# POWER_PCie.net
KiCad netlist of a schematic drawn in Altium Designer
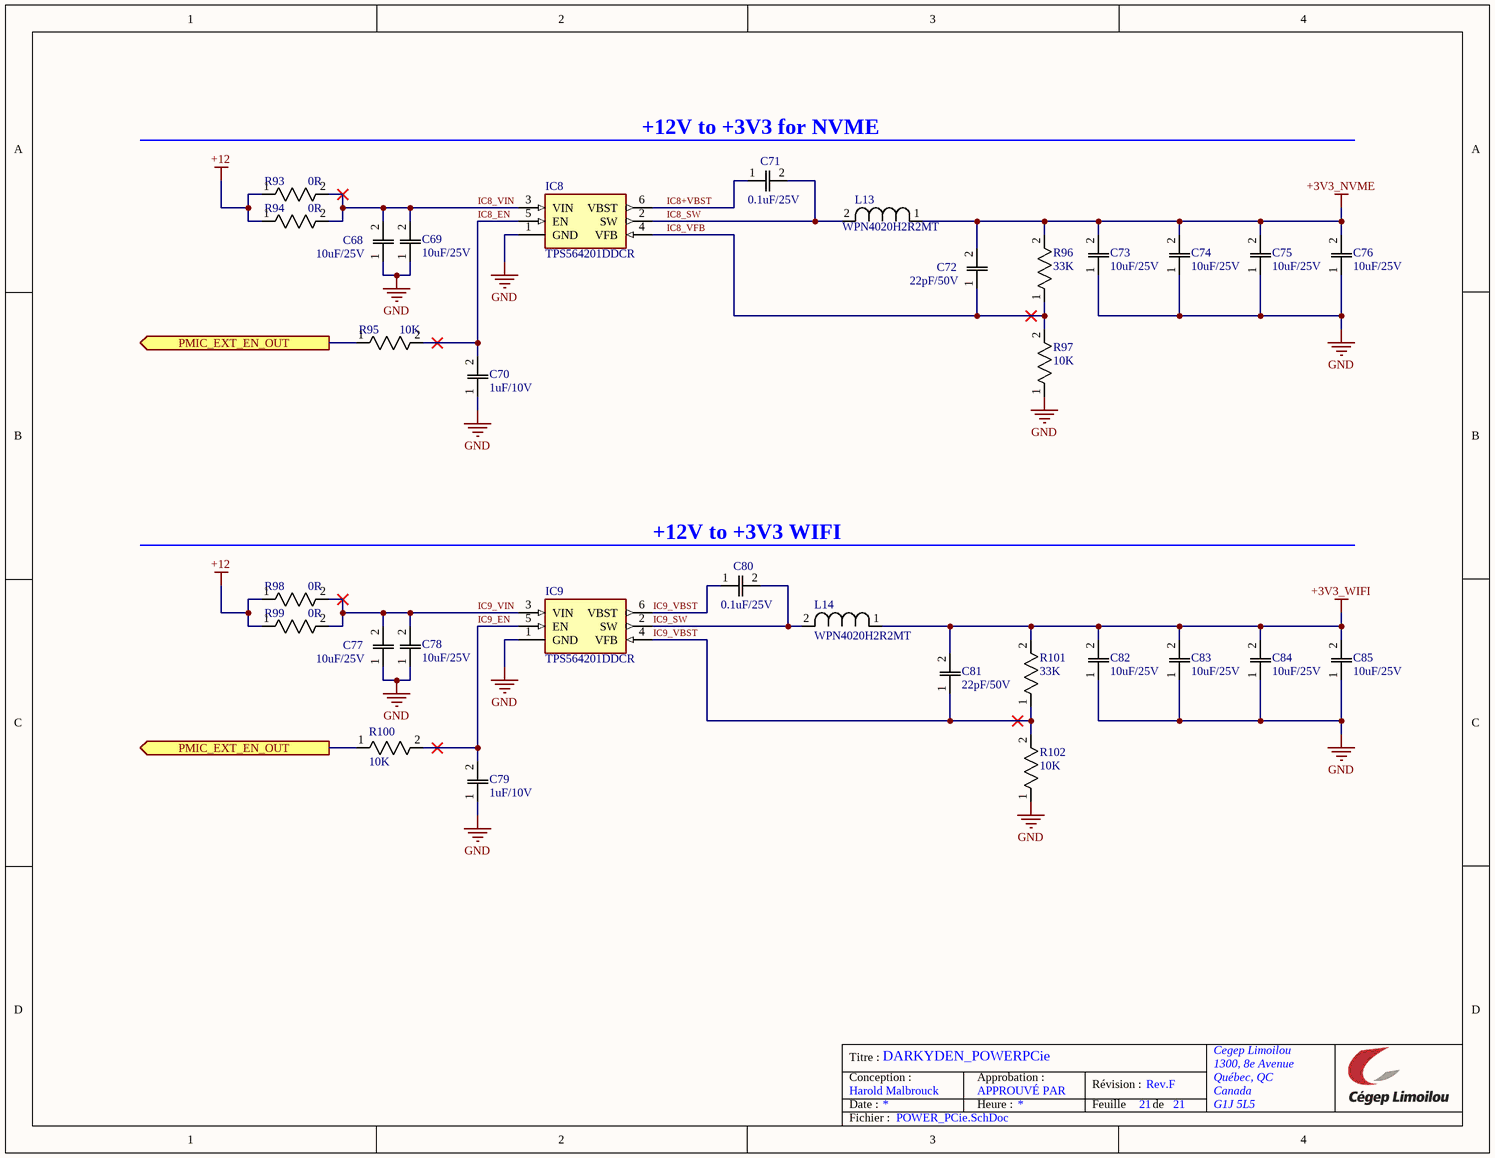
[diagram p0: POWER_PCie.SchDoc]

(export (version "E")
  (design (tool "Eeschema 10.0.6"))
  (components
    (comp (ref "C68")
      (value "10uF/25V")
      (footprint "C0805")
      (description "10uF / 25 VDC, +85degC, X5R Dielec, +/-10% ¦ KEMET C0805C106K3PACTU 0805")
      (fields
        (field (name "MANUFACTURER") "KEMET")
        (field (name "MANUFACTURER PART NUMBER") "C0805C106K3PACTU")
      )
      (libsource (lib "DARKYDEN") (part "C0805C106K3PACTU"))
    )
    (comp (ref "C69")
      (value "10uF/25V")
      (footprint "C0805")
      (description "10uF / 25 VDC, +85degC, X5R Dielec, +/-10% ¦ KEMET C0805C106K3PACTU 0805")
      (fields
        (field (name "MANUFACTURER") "KEMET")
        (field (name "MANUFACTURER PART NUMBER") "C0805C106K3PACTU")
      )
      (libsource (lib "DARKYDEN") (part "C0805C106K3PACTU"))
    )
    (comp (ref "C70")
      (value "1uF/10V")
      (footprint "C0805")
      (description "Multilayer Ceramic Capacitors MLCC - SMD/SMT 10V 1uF X7R 0805 10%")
      (fields
        (field (name "MANUFACTURER") "KEMET")
        (field (name "MANUFACTURER PART NUMBER") "C0805C105K3RACTU")
      )
      (libsource (lib "DARKYDEN") (part "C0805C105K8RACTU"))
    )
    (comp (ref "C71")
      (value "0.1uF/25V")
      (footprint "c0805")
      (description "0.1uF 25V X7R 10% SMD 0805 125C Plastic T/R")
      (fields
        (field (name "MANUFACTURER") "KEMET")
        (field (name "MANUFACTURER PART NUMBER") "C0805C104K5RACTU")
      )
      (libsource (lib "DARKYDEN") (part "C0805C104K3RACTU"))
    )
    (comp (ref "C72")
      (value "22pF/50V")
      (footprint "C0805")
      (description "Cap Ceramic 22pF 50V X7R 5% Pad SMD 0805 125°C T/R")
      (fields
        (field (name "MANUFACTURER") "KEMET")
        (field (name "MANUFACTURER PART NUMBER") "C0805C220J5RACTU")
      )
      (libsource (lib "DARKYDEN") (part "C0805C220J5RACTU"))
    )
    (comp (ref "C73")
      (value "10uF/25V")
      (footprint "C0805")
      (description "10uF / 25 VDC, +85degC, X5R Dielec, +/-10% ¦ KEMET C0805C106K3PACTU 0805")
      (fields
        (field (name "MANUFACTURER") "KEMET")
        (field (name "MANUFACTURER PART NUMBER") "C0805C106K3PACTU")
      )
      (libsource (lib "DARKYDEN") (part "C0805C106K3PACTU"))
    )
    (comp (ref "C74")
      (value "10uF/25V")
      (footprint "C0805")
      (description "10uF / 25 VDC, +85degC, X5R Dielec, +/-10% ¦ KEMET C0805C106K3PACTU 0805")
      (fields
        (field (name "MANUFACTURER") "KEMET")
        (field (name "MANUFACTURER PART NUMBER") "C0805C106K3PACTU")
      )
      (libsource (lib "DARKYDEN") (part "C0805C106K3PACTU"))
    )
    (comp (ref "C75")
      (value "10uF/25V")
      (footprint "C0805")
      (description "10uF / 25 VDC, +85degC, X5R Dielec, +/-10% ¦ KEMET C0805C106K3PACTU 0805")
      (fields
        (field (name "MANUFACTURER") "KEMET")
        (field (name "MANUFACTURER PART NUMBER") "C0805C106K3PACTU")
      )
      (libsource (lib "DARKYDEN") (part "C0805C106K3PACTU"))
    )
    (comp (ref "C76")
      (value "10uF/25V")
      (footprint "C0805")
      (description "10uF / 25 VDC, +85degC, X5R Dielec, +/-10% ¦ KEMET C0805C106K3PACTU 0805")
      (fields
        (field (name "MANUFACTURER") "KEMET")
        (field (name "MANUFACTURER PART NUMBER") "C0805C106K3PACTU")
      )
      (libsource (lib "DARKYDEN") (part "C0805C106K3PACTU"))
    )
    (comp (ref "C77")
      (value "10uF/25V")
      (footprint "C0805")
      (description "10uF / 25 VDC, +85degC, X5R Dielec, +/-10% ¦ KEMET C0805C106K3PACTU 0805")
      (fields
        (field (name "MANUFACTURER") "KEMET")
        (field (name "MANUFACTURER PART NUMBER") "C0805C106K3PACTU")
      )
      (libsource (lib "DARKYDEN") (part "C0805C106K3PACTU"))
    )
    (comp (ref "C78")
      (value "10uF/25V")
      (footprint "C0805")
      (description "10uF / 25 VDC, +85degC, X5R Dielec, +/-10% ¦ KEMET C0805C106K3PACTU 0805")
      (fields
        (field (name "MANUFACTURER") "KEMET")
        (field (name "MANUFACTURER PART NUMBER") "C0805C106K3PACTU")
      )
      (libsource (lib "DARKYDEN") (part "C0805C106K3PACTU"))
    )
    (comp (ref "C79")
      (value "1uF/10V")
      (footprint "C0805")
      (description "Multilayer Ceramic Capacitors MLCC - SMD/SMT 10V 1uF X7R 0805 10%")
      (fields
        (field (name "MANUFACTURER") "KEMET")
        (field (name "MANUFACTURER PART NUMBER") "C0805C105K3RACTU")
      )
      (libsource (lib "DARKYDEN") (part "C0805C105K8RACTU"))
    )
    (comp (ref "C80")
      (value "0.1uF/25V")
      (footprint "c0805")
      (description "0.1uF 25V X7R 10% SMD 0805 125C Plastic T/R")
      (fields
        (field (name "MANUFACTURER") "KEMET")
        (field (name "MANUFACTURER PART NUMBER") "C0805C104K5RACTU")
      )
      (libsource (lib "DARKYDEN") (part "C0805C104K3RACTU"))
    )
    (comp (ref "C81")
      (value "22pF/50V")
      (footprint "C0805")
      (description "Cap Ceramic 22pF 50V X7R 5% Pad SMD 0805 125°C T/R")
      (fields
        (field (name "MANUFACTURER") "KEMET")
        (field (name "MANUFACTURER PART NUMBER") "C0805C220J5RACTU")
      )
      (libsource (lib "DARKYDEN") (part "C0805C220J5RACTU"))
    )
    (comp (ref "C82")
      (value "10uF/25V")
      (footprint "C0805")
      (description "10uF / 25 VDC, +85degC, X5R Dielec, +/-10% ¦ KEMET C0805C106K3PACTU 0805")
      (fields
        (field (name "MANUFACTURER") "KEMET")
        (field (name "MANUFACTURER PART NUMBER") "C0805C106K3PACTU")
      )
      (libsource (lib "DARKYDEN") (part "C0805C106K3PACTU"))
    )
    (comp (ref "C83")
      (value "10uF/25V")
      (footprint "C0805")
      (description "10uF / 25 VDC, +85degC, X5R Dielec, +/-10% ¦ KEMET C0805C106K3PACTU 0805")
      (fields
        (field (name "MANUFACTURER") "KEMET")
        (field (name "MANUFACTURER PART NUMBER") "C0805C106K3PACTU")
      )
      (libsource (lib "DARKYDEN") (part "C0805C106K3PACTU"))
    )
    (comp (ref "C84")
      (value "10uF/25V")
      (footprint "C0805")
      (description "10uF / 25 VDC, +85degC, X5R Dielec, +/-10% ¦ KEMET C0805C106K3PACTU 0805")
      (fields
        (field (name "MANUFACTURER") "KEMET")
        (field (name "MANUFACTURER PART NUMBER") "C0805C106K3PACTU")
      )
      (libsource (lib "DARKYDEN") (part "C0805C106K3PACTU"))
    )
    (comp (ref "C85")
      (value "10uF/25V")
      (footprint "C0805")
      (description "10uF / 25 VDC, +85degC, X5R Dielec, +/-10% ¦ KEMET C0805C106K3PACTU 0805")
      (fields
        (field (name "MANUFACTURER") "KEMET")
        (field (name "MANUFACTURER PART NUMBER") "C0805C106K3PACTU")
      )
      (libsource (lib "DARKYDEN") (part "C0805C106K3PACTU"))
    )
    (comp (ref "IC8")
      (value "TPS564201DDCR")
      (footprint "SamacSys:SOT95P280X110-6N")
      (fields
        (field (name "MOUSER PART NUMBER") "595-TPS564201DDCR")
        (field (name "MANUFACTURER") "Texas Instruments")
      )
      (libsource (lib "SamacSys") (part "TPS564201DDCR"))
    )
    (comp (ref "IC9")
      (value "TPS564201DDCR")
      (footprint "SamacSys:SOT95P280X110-6N")
      (fields
        (field (name "MOUSER PART NUMBER") "595-TPS564201DDCR")
        (field (name "MANUFACTURER") "Texas Instruments")
      )
      (libsource (lib "SamacSys") (part "TPS564201DDCR"))
    )
    (comp (ref "L13")
      (value "WPN4020H2R2MT")
      (footprint "WPN4020H2R2MT:IND_WPN4020H_SNL")
      (description "2.2 µH Shielded Drum Core, Wirewound Inductor 4.3 A 48mOhm Max Nonstandard")
      (fields (field (name "MANUFACTURER") "Sunlord"))
      (libsource (lib "DARKYDEN") (part "WPN4020H2R2MT"))
    )
    (comp (ref "L14")
      (value "WPN4020H2R2MT")
      (footprint "WPN4020H2R2MT:IND_WPN4020H_SNL")
      (description "2.2 µH Shielded Drum Core, Wirewound Inductor 4.3 A 48mOhm Max Nonstandard")
      (fields (field (name "MANUFACTURER") "Sunlord"))
      (libsource (lib "DARKYDEN") (part "WPN4020H2R2MT"))
    )
    (comp (ref "R93")
      (value "0R")
      (footprint "SamacSys:RESC1608X55N")
      (description "Zero Ohm Resistor, Jumper, 0603 [1608 Metric], Thick Film, 100 mW, 1 A, Surface Mount")
      (fields
        (field (name "MOUSER PART NUMBER") "667-ERJ-3GEY0R00V")
        (field (name "ARROW PART NUMBER") "ERJ-3GEY0R00V")
      )
      (libsource (lib "DARKYDEN") (part "ERJ-3GEY0R00V"))
    )
    (comp (ref "R94")
      (value "0R")
      (footprint "SamacSys:RESC1608X55N")
      (description "Zero Ohm Resistor, Jumper, 0603 [1608 Metric], Thick Film, 100 mW, 1 A, Surface Mount")
      (fields
        (field (name "MOUSER PART NUMBER") "667-ERJ-3GEY0R00V")
        (field (name "ARROW PART NUMBER") "ERJ-3GEY0R00V")
      )
      (libsource (lib "DARKYDEN") (part "ERJ-3GEY0R00V"))
    )
    (comp (ref "R95")
      (value "10K")
      (footprint "SamacSys:RESC1608X55N")
      (description "10K Ohm 5% Res Thick Film 0603  0.1W(1/10W) ±200ppm/C Pad SMD Automotive T/R")
      (fields
        (field (name "MOUSER PART NUMBER") "667-ERJ-3GEYJ103V")
        (field (name "ARROW PART NUMBER") "ERJ-3GEYJ103V")
      )
      (libsource (lib "DARKYDEN") (part "ERJ-3GEYJ103V"))
    )
    (comp (ref "R96")
      (value "33K")
      (footprint "SamacSys:RESC1608X55N")
      (description "33K Ohm 0603  5% 0.1W(1/10W) +/-200ppm/ßC SMD Automotive T/R")
      (fields
        (field (name "MOUSER PART NUMBER") "667-ERJ-3GEYJ333V")
        (field (name "MANUFACTURER") "Panasonic")
      )
      (libsource (lib "DARKYDEN") (part "ERJ-3GEYJ333V"))
    )
    (comp (ref "R97")
      (value "10K")
      (footprint "SamacSys:RESC1608X55N")
      (description "10K Ohm 5% Res Thick Film 0603  0.1W(1/10W) ±200ppm/C Pad SMD Automotive T/R")
      (fields
        (field (name "MOUSER PART NUMBER") "667-ERJ-3GEYJ103V")
        (field (name "ARROW PART NUMBER") "ERJ-3GEYJ103V")
      )
      (libsource (lib "DARKYDEN") (part "ERJ-3GEYJ103V"))
    )
    (comp (ref "R98")
      (value "0R")
      (footprint "SamacSys:RESC1608X55N")
      (description "Zero Ohm Resistor, Jumper, 0603 [1608 Metric], Thick Film, 100 mW, 1 A, Surface Mount")
      (fields
        (field (name "MOUSER PART NUMBER") "667-ERJ-3GEY0R00V")
        (field (name "ARROW PART NUMBER") "ERJ-3GEY0R00V")
      )
      (libsource (lib "DARKYDEN") (part "ERJ-3GEY0R00V"))
    )
    (comp (ref "R99")
      (value "0R")
      (footprint "SamacSys:RESC1608X55N")
      (description "Zero Ohm Resistor, Jumper, 0603 [1608 Metric], Thick Film, 100 mW, 1 A, Surface Mount")
      (fields
        (field (name "MOUSER PART NUMBER") "667-ERJ-3GEY0R00V")
        (field (name "ARROW PART NUMBER") "ERJ-3GEY0R00V")
      )
      (libsource (lib "DARKYDEN") (part "ERJ-3GEY0R00V"))
    )
    (comp (ref "R100")
      (value "10K")
      (footprint "SamacSys:RESC1608X55N")
      (description "10K Ohm 5% Res Thick Film 0603  0.1W(1/10W) ±200ppm/C Pad SMD Automotive T/R")
      (fields
        (field (name "MOUSER PART NUMBER") "667-ERJ-3GEYJ103V")
        (field (name "ARROW PART NUMBER") "ERJ-3GEYJ103V")
      )
      (libsource (lib "DARKYDEN") (part "ERJ-3GEYJ103V"))
    )
    (comp (ref "R101")
      (value "33K")
      (footprint "SamacSys:RESC1608X55N")
      (description "33K Ohm 0603  5% 0.1W(1/10W) +/-200ppm/ßC SMD Automotive T/R")
      (fields
        (field (name "MOUSER PART NUMBER") "667-ERJ-3GEYJ333V")
        (field (name "MANUFACTURER") "Panasonic")
      )
      (libsource (lib "DARKYDEN") (part "ERJ-3GEYJ333V"))
    )
    (comp (ref "R102")
      (value "10K")
      (footprint "SamacSys:RESC1608X55N")
      (description "10K Ohm 5% Res Thick Film 0603  0.1W(1/10W) ±200ppm/C Pad SMD Automotive T/R")
      (fields
        (field (name "MOUSER PART NUMBER") "667-ERJ-3GEYJ103V")
        (field (name "ARROW PART NUMBER") "ERJ-3GEYJ103V")
      )
      (libsource (lib "DARKYDEN") (part "ERJ-3GEYJ103V"))
    )
  )
  (nets
    (net (code "1") (name "+3V3_NVME") (class "Default")
      (node (ref "C72") (pin "2") (pinfunction "2_2") (pintype "passive"))
      (node (ref "C73") (pin "2") (pinfunction "2_2") (pintype "passive"))
      (node (ref "C74") (pin "2") (pinfunction "2_2") (pintype "passive"))
      (node (ref "C75") (pin "2") (pinfunction "2_2") (pintype "passive"))
      (node (ref "C76") (pin "2") (pinfunction "2_2") (pintype "passive"))
      (node (ref "L13") (pin "1") (pinfunction "1_1") (pintype "passive"))
      (node (ref "R96") (pin "2") (pinfunction "2_2") (pintype "passive"))
    )
    (net (code "2") (name "+3V3_WIFI") (class "Default")
      (node (ref "C81") (pin "2") (pinfunction "2_2") (pintype "passive"))
      (node (ref "C82") (pin "2") (pinfunction "2_2") (pintype "passive"))
      (node (ref "C83") (pin "2") (pinfunction "2_2") (pintype "passive"))
      (node (ref "C84") (pin "2") (pinfunction "2_2") (pintype "passive"))
      (node (ref "C85") (pin "2") (pinfunction "2_2") (pintype "passive"))
      (node (ref "L14") (pin "1") (pinfunction "1_1") (pintype "passive"))
      (node (ref "R101") (pin "2") (pinfunction "2_2") (pintype "passive"))
    )
    (net (code "3") (name "+12") (class "Default")
      (node (ref "R93") (pin "1") (pinfunction "1_1") (pintype "passive"))
      (node (ref "R94") (pin "1") (pinfunction "1_1") (pintype "passive"))
      (node (ref "R98") (pin "1") (pinfunction "1_1") (pintype "passive"))
      (node (ref "R99") (pin "1") (pinfunction "1_1") (pintype "passive"))
    )
    (net (code "4") (name "/IC8+VBST") (class "Default")
      (node (ref "C71") (pin "1") (pinfunction "1_1") (pintype "passive"))
      (node (ref "IC8") (pin "6") (pinfunction "VBST_6") (pintype "output"))
    )
    (net (code "5") (name "/IC8_EN") (class "Default")
      (node (ref "C70") (pin "2") (pinfunction "2_2") (pintype "passive"))
      (node (ref "IC8") (pin "5") (pinfunction "EN_5") (pintype "input"))
      (node (ref "R95") (pin "2") (pinfunction "2_2") (pintype "passive"))
    )
    (net (code "6") (name "/IC8_SW") (class "Default")
      (node (ref "C71") (pin "2") (pinfunction "2_2") (pintype "passive"))
      (node (ref "IC8") (pin "2") (pinfunction "SW_2") (pintype "output"))
      (node (ref "L13") (pin "2") (pinfunction "2_2") (pintype "passive"))
    )
    (net (code "7") (name "/IC8_VFB") (class "Default")
      (node (ref "C72") (pin "1") (pinfunction "1_1") (pintype "passive"))
      (node (ref "IC8") (pin "4") (pinfunction "VFB_4") (pintype "input"))
      (node (ref "R96") (pin "1") (pinfunction "1_1") (pintype "passive"))
      (node (ref "R97") (pin "2") (pinfunction "2_2") (pintype "passive"))
    )
    (net (code "8") (name "/IC8_VIN") (class "Default")
      (node (ref "C68") (pin "2") (pinfunction "2_2") (pintype "passive"))
      (node (ref "C69") (pin "2") (pinfunction "2_2") (pintype "passive"))
      (node (ref "IC8") (pin "3") (pinfunction "VIN_3") (pintype "input"))
      (node (ref "R93") (pin "2") (pinfunction "2_2") (pintype "passive"))
      (node (ref "R94") (pin "2") (pinfunction "2_2") (pintype "passive"))
    )
    (net (code "9") (name "/IC9_EN") (class "Default")
      (node (ref "C79") (pin "2") (pinfunction "2_2") (pintype "passive"))
      (node (ref "IC9") (pin "5") (pinfunction "EN_5") (pintype "input"))
      (node (ref "R100") (pin "2") (pinfunction "2_2") (pintype "passive"))
    )
    (net (code "10") (name "/IC9_SW") (class "Default")
      (node (ref "C80") (pin "2") (pinfunction "2_2") (pintype "passive"))
      (node (ref "IC9") (pin "2") (pinfunction "SW_2") (pintype "output"))
      (node (ref "L14") (pin "2") (pinfunction "2_2") (pintype "passive"))
    )
    (net (code "11") (name "/IC9_VBST") (class "Default")
      (node (ref "C80") (pin "1") (pinfunction "1_1") (pintype "passive"))
      (node (ref "C81") (pin "1") (pinfunction "1_1") (pintype "passive"))
      (node (ref "IC9") (pin "4") (pinfunction "VFB_4") (pintype "input"))
      (node (ref "IC9") (pin "6") (pinfunction "VBST_6") (pintype "output"))
      (node (ref "R101") (pin "1") (pinfunction "1_1") (pintype "passive"))
      (node (ref "R102") (pin "2") (pinfunction "2_2") (pintype "passive"))
    )
    (net (code "12") (name "/IC9_VIN") (class "Default")
      (node (ref "C77") (pin "2") (pinfunction "2_2") (pintype "passive"))
      (node (ref "C78") (pin "2") (pinfunction "2_2") (pintype "passive"))
      (node (ref "IC9") (pin "3") (pinfunction "VIN_3") (pintype "input"))
      (node (ref "R98") (pin "2") (pinfunction "2_2") (pintype "passive"))
      (node (ref "R99") (pin "2") (pinfunction "2_2") (pintype "passive"))
    )
    (net (code "13") (name "/PMIC_EXT_EN_OUT") (class "Default")
      (node (ref "R100") (pin "1") (pinfunction "1_1") (pintype "passive"))
      (node (ref "R95") (pin "1") (pinfunction "1_1") (pintype "passive"))
    )
    (net (code "14") (name "GND") (class "Default")
      (node (ref "C68") (pin "1") (pinfunction "1_1") (pintype "passive"))
      (node (ref "C69") (pin "1") (pinfunction "1_1") (pintype "passive"))
      (node (ref "C70") (pin "1") (pinfunction "1_1") (pintype "passive"))
      (node (ref "C73") (pin "1") (pinfunction "1_1") (pintype "passive"))
      (node (ref "C74") (pin "1") (pinfunction "1_1") (pintype "passive"))
      (node (ref "C75") (pin "1") (pinfunction "1_1") (pintype "passive"))
      (node (ref "C76") (pin "1") (pinfunction "1_1") (pintype "passive"))
      (node (ref "C77") (pin "1") (pinfunction "1_1") (pintype "passive"))
      (node (ref "C78") (pin "1") (pinfunction "1_1") (pintype "passive"))
      (node (ref "C79") (pin "1") (pinfunction "1_1") (pintype "passive"))
      (node (ref "C82") (pin "1") (pinfunction "1_1") (pintype "passive"))
      (node (ref "C83") (pin "1") (pinfunction "1_1") (pintype "passive"))
      (node (ref "C84") (pin "1") (pinfunction "1_1") (pintype "passive"))
      (node (ref "C85") (pin "1") (pinfunction "1_1") (pintype "passive"))
      (node (ref "IC8") (pin "1") (pinfunction "GND_1") (pintype "passive"))
      (node (ref "IC9") (pin "1") (pinfunction "GND_1") (pintype "passive"))
      (node (ref "R102") (pin "1") (pinfunction "1_1") (pintype "passive"))
      (node (ref "R97") (pin "1") (pinfunction "1_1") (pintype "passive"))
    )
  )
)
